# UniversalBoardBreakout_Pogo.net
KiCad netlist of a schematic drawn in EAGLE
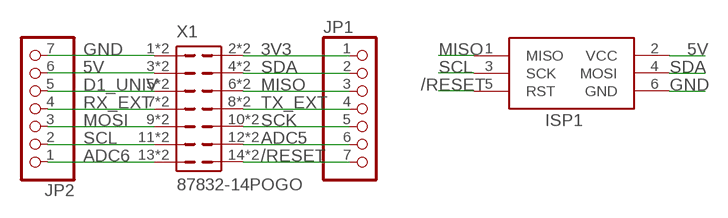
[diagram p0: schematic, sheet 1]

(export (version "E")
  (design (tool "Eeschema 10.0.6"))
  (components
    (comp (ref "ISP1")
      (value "AVRISP-6")
      (footprint "eagle-import:AVRISP")
      (libsource (lib "eagle-import") (part "AVRISP-6"))
    )
    (comp (ref "JP1")
      (value "CONN_7")
      (footprint "eagle-import:1X07")
      (libsource (lib "eagle-import") (part "CONN_7"))
    )
    (comp (ref "JP2")
      (value "CONN_7")
      (footprint "eagle-import:1X07")
      (libsource (lib "eagle-import") (part "CONN_7"))
    )
    (comp (ref "X1")
      (value "87832-14POGO")
      (footprint "eagle-import:87832-14_POGO")
      (libsource (lib "eagle-import") (part "87832-14POGO"))
    )
  )
  (nets
    (net (code "1") (name "/3V3") (class "Default")
      (node (ref "JP1") (pin "1") (pinfunction "1_1") (pintype "passive"))
      (node (ref "X1") (pin "2") (pinfunction "2_2") (pintype "passive"))
      (node (ref "X1") (pin "P2") (pinfunction "2_P2") (pintype "passive"))
    )
    (net (code "2") (name "/5V") (class "Default")
      (node (ref "ISP1") (pin "2") (pinfunction "VCC_2") (pintype "power_in"))
      (node (ref "JP2") (pin "6") (pinfunction "6_6") (pintype "passive"))
      (node (ref "X1") (pin "3") (pinfunction "3_3") (pintype "passive"))
      (node (ref "X1") (pin "P3") (pinfunction "3_P3") (pintype "passive"))
    )
    (net (code "3") (name "/ADC5") (class "Default")
      (node (ref "JP1") (pin "6") (pinfunction "6_6") (pintype "passive"))
      (node (ref "X1") (pin "12") (pinfunction "12_12") (pintype "passive"))
      (node (ref "X1") (pin "P12") (pinfunction "12_P12") (pintype "passive"))
    )
    (net (code "4") (name "/ADC6") (class "Default")
      (node (ref "JP2") (pin "1") (pinfunction "1_1") (pintype "passive"))
      (node (ref "X1") (pin "13") (pinfunction "13_13") (pintype "passive"))
      (node (ref "X1") (pin "P13") (pinfunction "13_P13") (pintype "passive"))
    )
    (net (code "5") (name "/D1_UNIV") (class "Default")
      (node (ref "JP2") (pin "5") (pinfunction "5_5") (pintype "passive"))
      (node (ref "X1") (pin "5") (pinfunction "5_5") (pintype "passive"))
      (node (ref "X1") (pin "P5") (pinfunction "5_P5") (pintype "passive"))
    )
    (net (code "6") (name "/GND") (class "Default")
      (node (ref "ISP1") (pin "6") (pinfunction "GND_6") (pintype "power_in"))
      (node (ref "JP2") (pin "7") (pinfunction "7_7") (pintype "passive"))
      (node (ref "X1") (pin "1") (pinfunction "1_1") (pintype "passive"))
      (node (ref "X1") (pin "P1") (pinfunction "1_P1") (pintype "passive"))
    )
    (net (code "7") (name "/MISO") (class "Default")
      (node (ref "ISP1") (pin "1") (pinfunction "MISO_1") (pintype "input"))
      (node (ref "JP1") (pin "3") (pinfunction "3_3") (pintype "passive"))
      (node (ref "X1") (pin "6") (pinfunction "6_6") (pintype "passive"))
      (node (ref "X1") (pin "P6") (pinfunction "6_P6") (pintype "passive"))
    )
    (net (code "8") (name "/MOSI") (class "Default")
      (node (ref "JP2") (pin "3") (pinfunction "3_3") (pintype "passive"))
      (node (ref "X1") (pin "9") (pinfunction "9_9") (pintype "passive"))
      (node (ref "X1") (pin "P9") (pinfunction "9_P9") (pintype "passive"))
    )
    (net (code "9") (name "/RX_EXT") (class "Default")
      (node (ref "JP2") (pin "4") (pinfunction "4_4") (pintype "passive"))
      (node (ref "X1") (pin "7") (pinfunction "7_7") (pintype "passive"))
      (node (ref "X1") (pin "P7") (pinfunction "7_P7") (pintype "passive"))
    )
    (net (code "10") (name "/SCK") (class "Default")
      (node (ref "JP1") (pin "5") (pinfunction "5_5") (pintype "passive"))
      (node (ref "X1") (pin "10") (pinfunction "10_10") (pintype "passive"))
      (node (ref "X1") (pin "P10") (pinfunction "10_P10") (pintype "passive"))
    )
    (net (code "11") (name "/SCL") (class "Default")
      (node (ref "ISP1") (pin "3") (pinfunction "SCK_3") (pintype "output"))
      (node (ref "JP2") (pin "2") (pinfunction "2_2") (pintype "passive"))
      (node (ref "X1") (pin "11") (pinfunction "11_11") (pintype "passive"))
      (node (ref "X1") (pin "P11") (pinfunction "11_P11") (pintype "passive"))
    )
    (net (code "12") (name "/SDA") (class "Default")
      (node (ref "ISP1") (pin "4") (pinfunction "MOSI_4") (pintype "output"))
      (node (ref "JP1") (pin "2") (pinfunction "2_2") (pintype "passive"))
      (node (ref "X1") (pin "4") (pinfunction "4_4") (pintype "passive"))
      (node (ref "X1") (pin "P4") (pinfunction "4_P4") (pintype "passive"))
    )
    (net (code "13") (name "/TX_EXT") (class "Default")
      (node (ref "JP1") (pin "4") (pinfunction "4_4") (pintype "passive"))
      (node (ref "X1") (pin "8") (pinfunction "8_8") (pintype "passive"))
      (node (ref "X1") (pin "P8") (pinfunction "8_P8") (pintype "passive"))
    )
    (net (code "14") (name "/{slash}RESET") (class "Default")
      (node (ref "ISP1") (pin "5") (pinfunction "RST_5") (pintype "output"))
      (node (ref "JP1") (pin "7") (pinfunction "7_7") (pintype "passive"))
      (node (ref "X1") (pin "14") (pinfunction "14_14") (pintype "passive"))
      (node (ref "X1") (pin "P14") (pinfunction "14_P14") (pintype "passive"))
    )
  )
)
